# AFM_Power_board__ALL_SMD.net
KiCad netlist of a schematic drawn in EAGLE
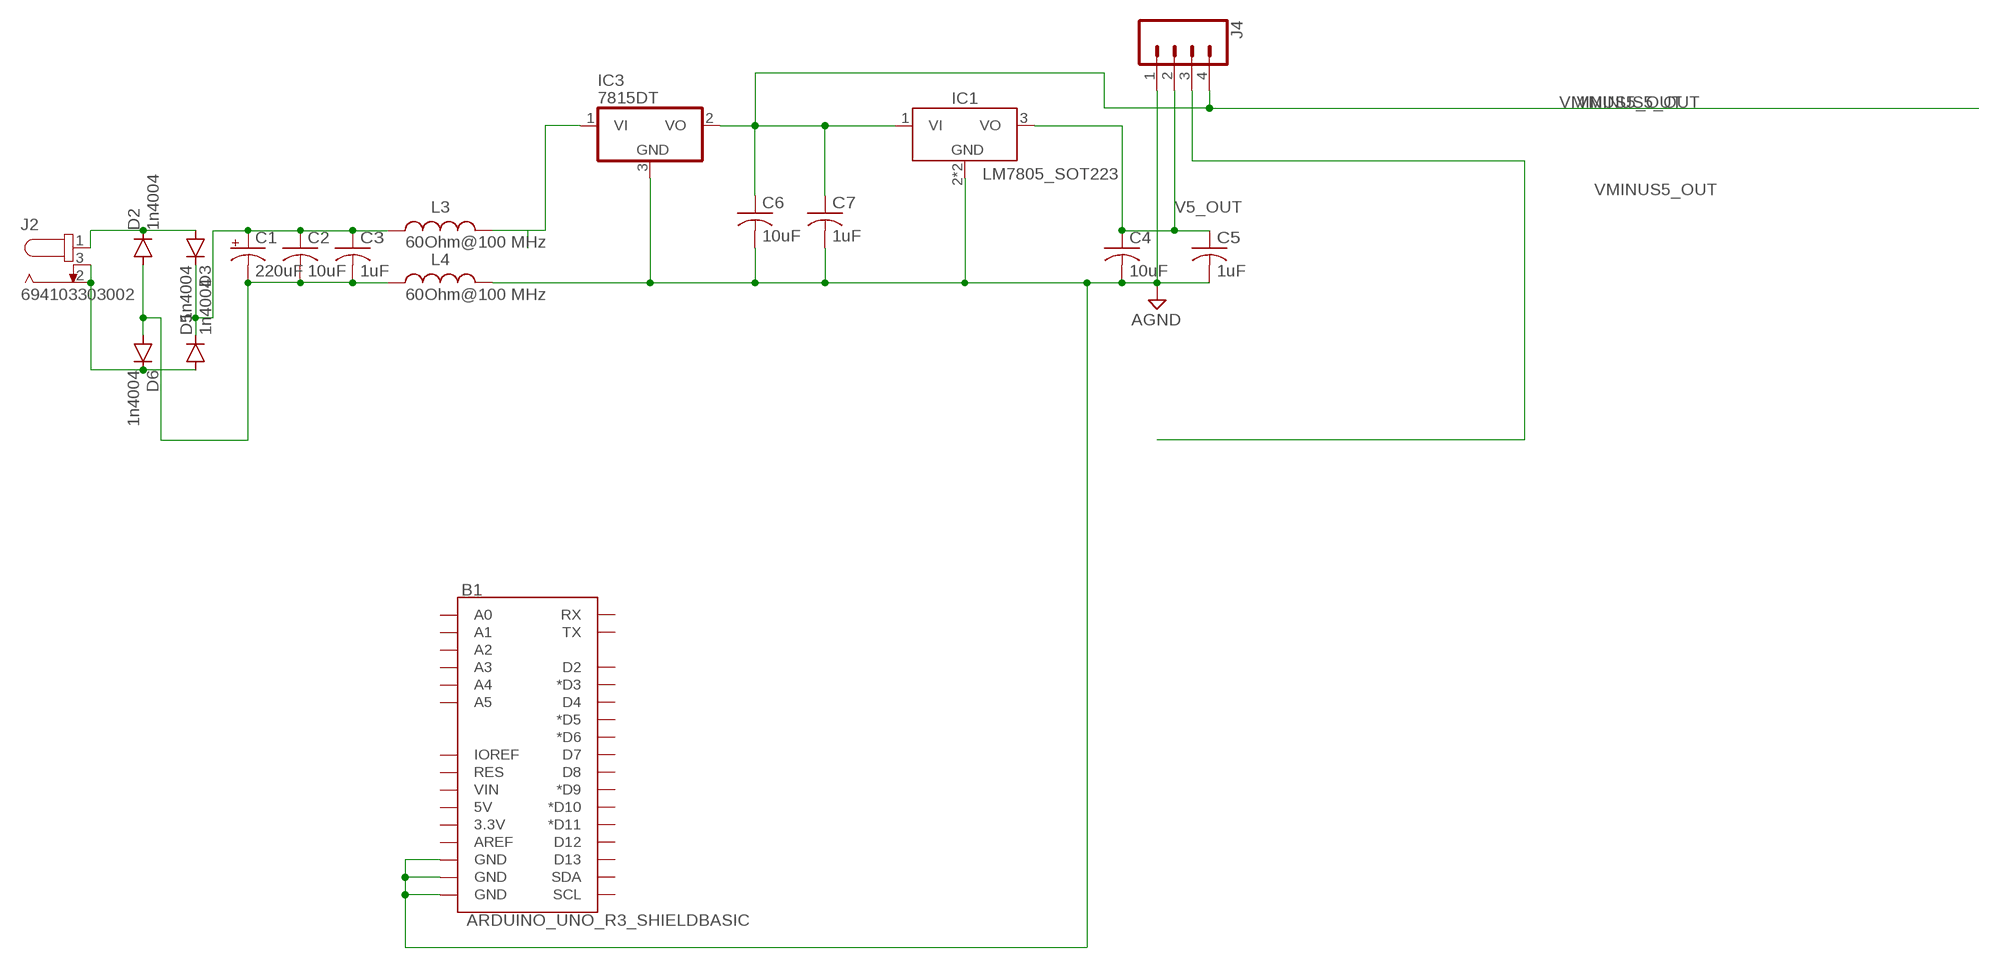
[diagram p0: schematic, sheet 1]

(export (version "E")
  (design (tool "Eeschema 10.0.6"))
  (components
    (comp (ref "B1")
      (value "ARDUINO_UNO_R3_SHIELDBASIC")
      (footprint "eagle-import:UNO_R3_SHIELD")
      (libsource (lib "eagle-import") (part "ARDUINO_UNO_R3_SHIELDBASIC"))
    )
    (comp (ref "C1")
      (value "220uF")
      (footprint "eagle-import:E5-8,5")
      (libsource (lib "eagle-import") (part "CAPACITOR-PE5-8.5"))
    )
    (comp (ref "C2")
      (value "10uF")
      (footprint "eagle-import:C050-024X044")
      (libsource (lib "eagle-import") (part "C-US050-024X044"))
    )
    (comp (ref "C3")
      (value "1uF")
      (footprint "eagle-import:C050-024X044")
      (libsource (lib "eagle-import") (part "C-US050-024X044"))
    )
    (comp (ref "C4")
      (value "10uF")
      (footprint "eagle-import:C050-024X044")
      (libsource (lib "eagle-import") (part "C-US050-024X044"))
    )
    (comp (ref "C5")
      (value "1uF")
      (footprint "eagle-import:C050-024X044")
      (libsource (lib "eagle-import") (part "C-US050-024X044"))
    )
    (comp (ref "C6")
      (value "10uF")
      (footprint "eagle-import:C050-024X044")
      (libsource (lib "eagle-import") (part "C-US050-024X044"))
    )
    (comp (ref "C7")
      (value "1uF")
      (footprint "eagle-import:C050-024X044")
      (libsource (lib "eagle-import") (part "C-US050-024X044"))
    )
    (comp (ref "D2")
      (value "1n4004")
      (footprint "eagle-import:SOD123")
      (libsource (lib "eagle-import") (part "DIODE-SOD123"))
    )
    (comp (ref "D3")
      (value "1n4004")
      (footprint "eagle-import:SOD123")
      (libsource (lib "eagle-import") (part "DIODE-SOD123"))
    )
    (comp (ref "D5")
      (value "1n4004")
      (footprint "eagle-import:SOD123")
      (libsource (lib "eagle-import") (part "DIODE-SOD123"))
    )
    (comp (ref "D6")
      (value "1n4004")
      (footprint "eagle-import:SOD123")
      (libsource (lib "eagle-import") (part "DIODE-SOD123"))
    )
    (comp (ref "IC1")
      (value "LM7805_SOT223")
      (footprint "eagle-import:SOT230P700X170-4")
      (fields (field (name "MANUFACTURER") "Generic"))
      (libsource (lib "eagle-import") (part "LM7805_SOT223"))
    )
    (comp (ref "IC3")
      (value "7815DT")
      (footprint "eagle-import:TO252")
      (libsource (lib "eagle-import") (part "78DT15"))
    )
    (comp (ref "J2")
      (value "694103303002")
      (footprint "eagle-import:694103303002")
      (fields
        (field (name "DIGIKEY_PART_NUMBER") "732-5925-ND")
        (field (name "MANUFACTURER") "Wurth Electronics Inc.")
        (field (name "CREATED_BY") "PCBLayout.com")
      )
      (libsource (lib "eagle-import") (part "694103303002"))
    )
    (comp (ref "J4")
      (value "CONN_04LONGPADS")
      (footprint "eagle-import:1X04_LONGPADS")
      (libsource (lib "eagle-import") (part "CONN_04LONGPADS"))
    )
    (comp (ref "L3")
      (value "60Ohm@100 MHz")
      (footprint "eagle-import:WE-CBF_0603_W2.2")
      (libsource (lib "eagle-import") (part "WE-CBF_0603_WB_HS_74279267"))
    )
    (comp (ref "L4")
      (value "60Ohm@100 MHz")
      (footprint "eagle-import:WE-CBF_0603_W2.2")
      (libsource (lib "eagle-import") (part "WE-CBF_0603_WB_HS_74279267"))
    )
  )
  (nets
    (net (code "1") (name "/V5_OUT") (class "Default")
      (node (ref "C4") (pin "1") (pinfunction "1_1") (pintype "passive"))
      (node (ref "C5") (pin "1") (pinfunction "1_1") (pintype "passive"))
      (node (ref "IC1") (pin "3") (pinfunction "VO_3") (pintype "output"))
      (node (ref "J4") (pin "2") (pinfunction "2_2") (pintype "passive"))
    )
    (net (code "2") (name "/VMINUS5_OUT") (class "Default")
      (node (ref "J4") (pin "3") (pinfunction "3_3") (pintype "passive"))
    )
    (net (code "3") (name "AGND") (class "Default")
      (node (ref "B1") (pin "GND@0") (pinfunction "GND_GND@0") (pintype "bidirectional"))
      (node (ref "B1") (pin "GND@1") (pinfunction "GND_GND@1") (pintype "bidirectional"))
      (node (ref "B1") (pin "GND@2") (pinfunction "GND_GND@2") (pintype "bidirectional"))
      (node (ref "C4") (pin "2") (pinfunction "2_2") (pintype "passive"))
      (node (ref "C5") (pin "2") (pinfunction "2_2") (pintype "passive"))
      (node (ref "C6") (pin "2") (pinfunction "2_2") (pintype "passive"))
      (node (ref "C7") (pin "2") (pinfunction "2_2") (pintype "passive"))
      (node (ref "IC1") (pin "2") (pinfunction "GND_2") (pintype "passive"))
      (node (ref "IC1") (pin "4") (pinfunction "GND_4") (pintype "passive"))
      (node (ref "IC3") (pin "3") (pinfunction "GND_3") (pintype "passive"))
      (node (ref "J4") (pin "1") (pinfunction "1_1") (pintype "passive"))
      (node (ref "L4") (pin "2") (pinfunction "2_2") (pintype "passive"))
    )
    (net (code "4") (name "Net-(C1-Pad+)") (class "Default")
      (node (ref "C1") (pin "+") (pinfunction "+_+") (pintype "passive"))
      (node (ref "C2") (pin "1") (pinfunction "1_1") (pintype "passive"))
      (node (ref "C3") (pin "1") (pinfunction "1_1") (pintype "passive"))
      (node (ref "D3") (pin "C") (pinfunction "C_C") (pintype "passive"))
      (node (ref "D5") (pin "C") (pinfunction "C_C") (pintype "passive"))
      (node (ref "L3") (pin "1") (pinfunction "1_1") (pintype "passive"))
    )
    (net (code "5") (name "Net-(C1-Pad-)") (class "Default")
      (node (ref "C1") (pin "-") (pinfunction "-_-") (pintype "passive"))
      (node (ref "C2") (pin "2") (pinfunction "2_2") (pintype "passive"))
      (node (ref "C3") (pin "2") (pinfunction "2_2") (pintype "passive"))
      (node (ref "D2") (pin "A") (pinfunction "A_A") (pintype "passive"))
      (node (ref "D6") (pin "A") (pinfunction "A_A") (pintype "passive"))
      (node (ref "L4") (pin "1") (pinfunction "1_1") (pintype "passive"))
    )
    (net (code "6") (name "Net-(D2-PadC)") (class "Default")
      (node (ref "D2") (pin "C") (pinfunction "C_C") (pintype "passive"))
      (node (ref "D3") (pin "A") (pinfunction "A_A") (pintype "passive"))
      (node (ref "J2") (pin "1") (pinfunction "1_1") (pintype "passive"))
    )
    (net (code "7") (name "Net-(D5-PadA)") (class "Default")
      (node (ref "D5") (pin "A") (pinfunction "A_A") (pintype "passive"))
      (node (ref "D6") (pin "C") (pinfunction "C_C") (pintype "passive"))
      (node (ref "J2") (pin "2") (pinfunction "2_2") (pintype "passive"))
      (node (ref "J2") (pin "3") (pinfunction "3_3") (pintype "passive"))
    )
    (net (code "8") (name "Net-(IC1-VI)") (class "Default")
      (node (ref "C6") (pin "1") (pinfunction "1_1") (pintype "passive"))
      (node (ref "C7") (pin "1") (pinfunction "1_1") (pintype "passive"))
      (node (ref "IC1") (pin "1") (pinfunction "VI_1") (pintype "input"))
      (node (ref "IC3") (pin "2") (pinfunction "VO_2") (pintype "passive"))
      (node (ref "J4") (pin "4") (pinfunction "4_4") (pintype "passive"))
    )
    (net (code "9") (name "Net-(IC3-VI)") (class "Default")
      (node (ref "IC3") (pin "1") (pinfunction "VI_1") (pintype "input"))
      (node (ref "L3") (pin "2") (pinfunction "2_2") (pintype "passive"))
    )
    (net (code "10") (name "unconnected-(B1-*D3-PadD3)") (class "Default")
      (node (ref "B1") (pin "D3") (pinfunction "*D3_D3") (pintype "bidirectional"))
    )
    (net (code "11") (name "unconnected-(B1-*D5-PadD5)") (class "Default")
      (node (ref "B1") (pin "D5") (pinfunction "*D5_D5") (pintype "bidirectional"))
    )
    (net (code "12") (name "unconnected-(B1-*D6-PadD6)") (class "Default")
      (node (ref "B1") (pin "D6") (pinfunction "*D6_D6") (pintype "bidirectional"))
    )
    (net (code "13") (name "unconnected-(B1-*D9-PadD9)") (class "Default")
      (node (ref "B1") (pin "D9") (pinfunction "*D9_D9") (pintype "bidirectional"))
    )
    (net (code "14") (name "unconnected-(B1-*D10-PadD10)") (class "Default")
      (node (ref "B1") (pin "D10") (pinfunction "*D10_D10") (pintype "bidirectional"))
    )
    (net (code "15") (name "unconnected-(B1-*D11-PadD11)") (class "Default")
      (node (ref "B1") (pin "D11") (pinfunction "*D11_D11") (pintype "bidirectional"))
    )
    (net (code "16") (name "unconnected-(B1-Pad3.3V)") (class "Default")
      (node (ref "B1") (pin "3.3V") (pinfunction "3.3V_3.3V") (pintype "bidirectional"))
    )
    (net (code "17") (name "unconnected-(B1-Pad5V)") (class "Default")
      (node (ref "B1") (pin "5V") (pinfunction "5V_5V") (pintype "bidirectional"))
    )
    (net (code "18") (name "unconnected-(B1-PadA0)") (class "Default")
      (node (ref "B1") (pin "A0") (pinfunction "A0_A0") (pintype "bidirectional"))
    )
    (net (code "19") (name "unconnected-(B1-PadA1)") (class "Default")
      (node (ref "B1") (pin "A1") (pinfunction "A1_A1") (pintype "bidirectional"))
    )
    (net (code "20") (name "unconnected-(B1-PadA2)") (class "Default")
      (node (ref "B1") (pin "A2") (pinfunction "A2_A2") (pintype "bidirectional"))
    )
    (net (code "21") (name "unconnected-(B1-PadA3)") (class "Default")
      (node (ref "B1") (pin "A3") (pinfunction "A3_A3") (pintype "bidirectional"))
    )
    (net (code "22") (name "unconnected-(B1-PadA4)") (class "Default")
      (node (ref "B1") (pin "A4") (pinfunction "A4_A4") (pintype "bidirectional"))
    )
    (net (code "23") (name "unconnected-(B1-PadA5)") (class "Default")
      (node (ref "B1") (pin "A5") (pinfunction "A5_A5") (pintype "bidirectional"))
    )
    (net (code "24") (name "unconnected-(B1-PadAREF)") (class "Default")
      (node (ref "B1") (pin "AREF") (pinfunction "AREF_AREF") (pintype "bidirectional"))
    )
    (net (code "25") (name "unconnected-(B1-PadD2)") (class "Default")
      (node (ref "B1") (pin "D2") (pinfunction "D2_D2") (pintype "bidirectional"))
    )
    (net (code "26") (name "unconnected-(B1-PadD4)") (class "Default")
      (node (ref "B1") (pin "D4") (pinfunction "D4_D4") (pintype "bidirectional"))
    )
    (net (code "27") (name "unconnected-(B1-PadD7)") (class "Default")
      (node (ref "B1") (pin "D7") (pinfunction "D7_D7") (pintype "bidirectional"))
    )
    (net (code "28") (name "unconnected-(B1-PadD8)") (class "Default")
      (node (ref "B1") (pin "D8") (pinfunction "D8_D8") (pintype "bidirectional"))
    )
    (net (code "29") (name "unconnected-(B1-PadD12)") (class "Default")
      (node (ref "B1") (pin "D12") (pinfunction "D12_D12") (pintype "bidirectional"))
    )
    (net (code "30") (name "unconnected-(B1-PadD13)") (class "Default")
      (node (ref "B1") (pin "D13") (pinfunction "D13_D13") (pintype "bidirectional"))
    )
    (net (code "31") (name "unconnected-(B1-PadIOREF)") (class "Default")
      (node (ref "B1") (pin "IOREF") (pinfunction "IOREF_IOREF") (pintype "bidirectional"))
    )
    (net (code "32") (name "unconnected-(B1-PadRES)") (class "Default")
      (node (ref "B1") (pin "RES") (pinfunction "RES_RES") (pintype "bidirectional"))
    )
    (net (code "33") (name "unconnected-(B1-PadRX)") (class "Default")
      (node (ref "B1") (pin "RX") (pinfunction "RX_RX") (pintype "bidirectional"))
    )
    (net (code "34") (name "unconnected-(B1-PadSCL)") (class "Default")
      (node (ref "B1") (pin "SCL") (pinfunction "SCL_SCL") (pintype "bidirectional"))
    )
    (net (code "35") (name "unconnected-(B1-PadSDA)") (class "Default")
      (node (ref "B1") (pin "SDA") (pinfunction "SDA_SDA") (pintype "bidirectional"))
    )
    (net (code "36") (name "unconnected-(B1-PadTX)") (class "Default")
      (node (ref "B1") (pin "TX") (pinfunction "TX_TX") (pintype "bidirectional"))
    )
    (net (code "37") (name "unconnected-(B1-PadVIN)") (class "Default")
      (node (ref "B1") (pin "VIN") (pinfunction "VIN_VIN") (pintype "bidirectional"))
    )
  )
)
